# IO_function.net
KiCad netlist of a schematic drawn in Altium Designer
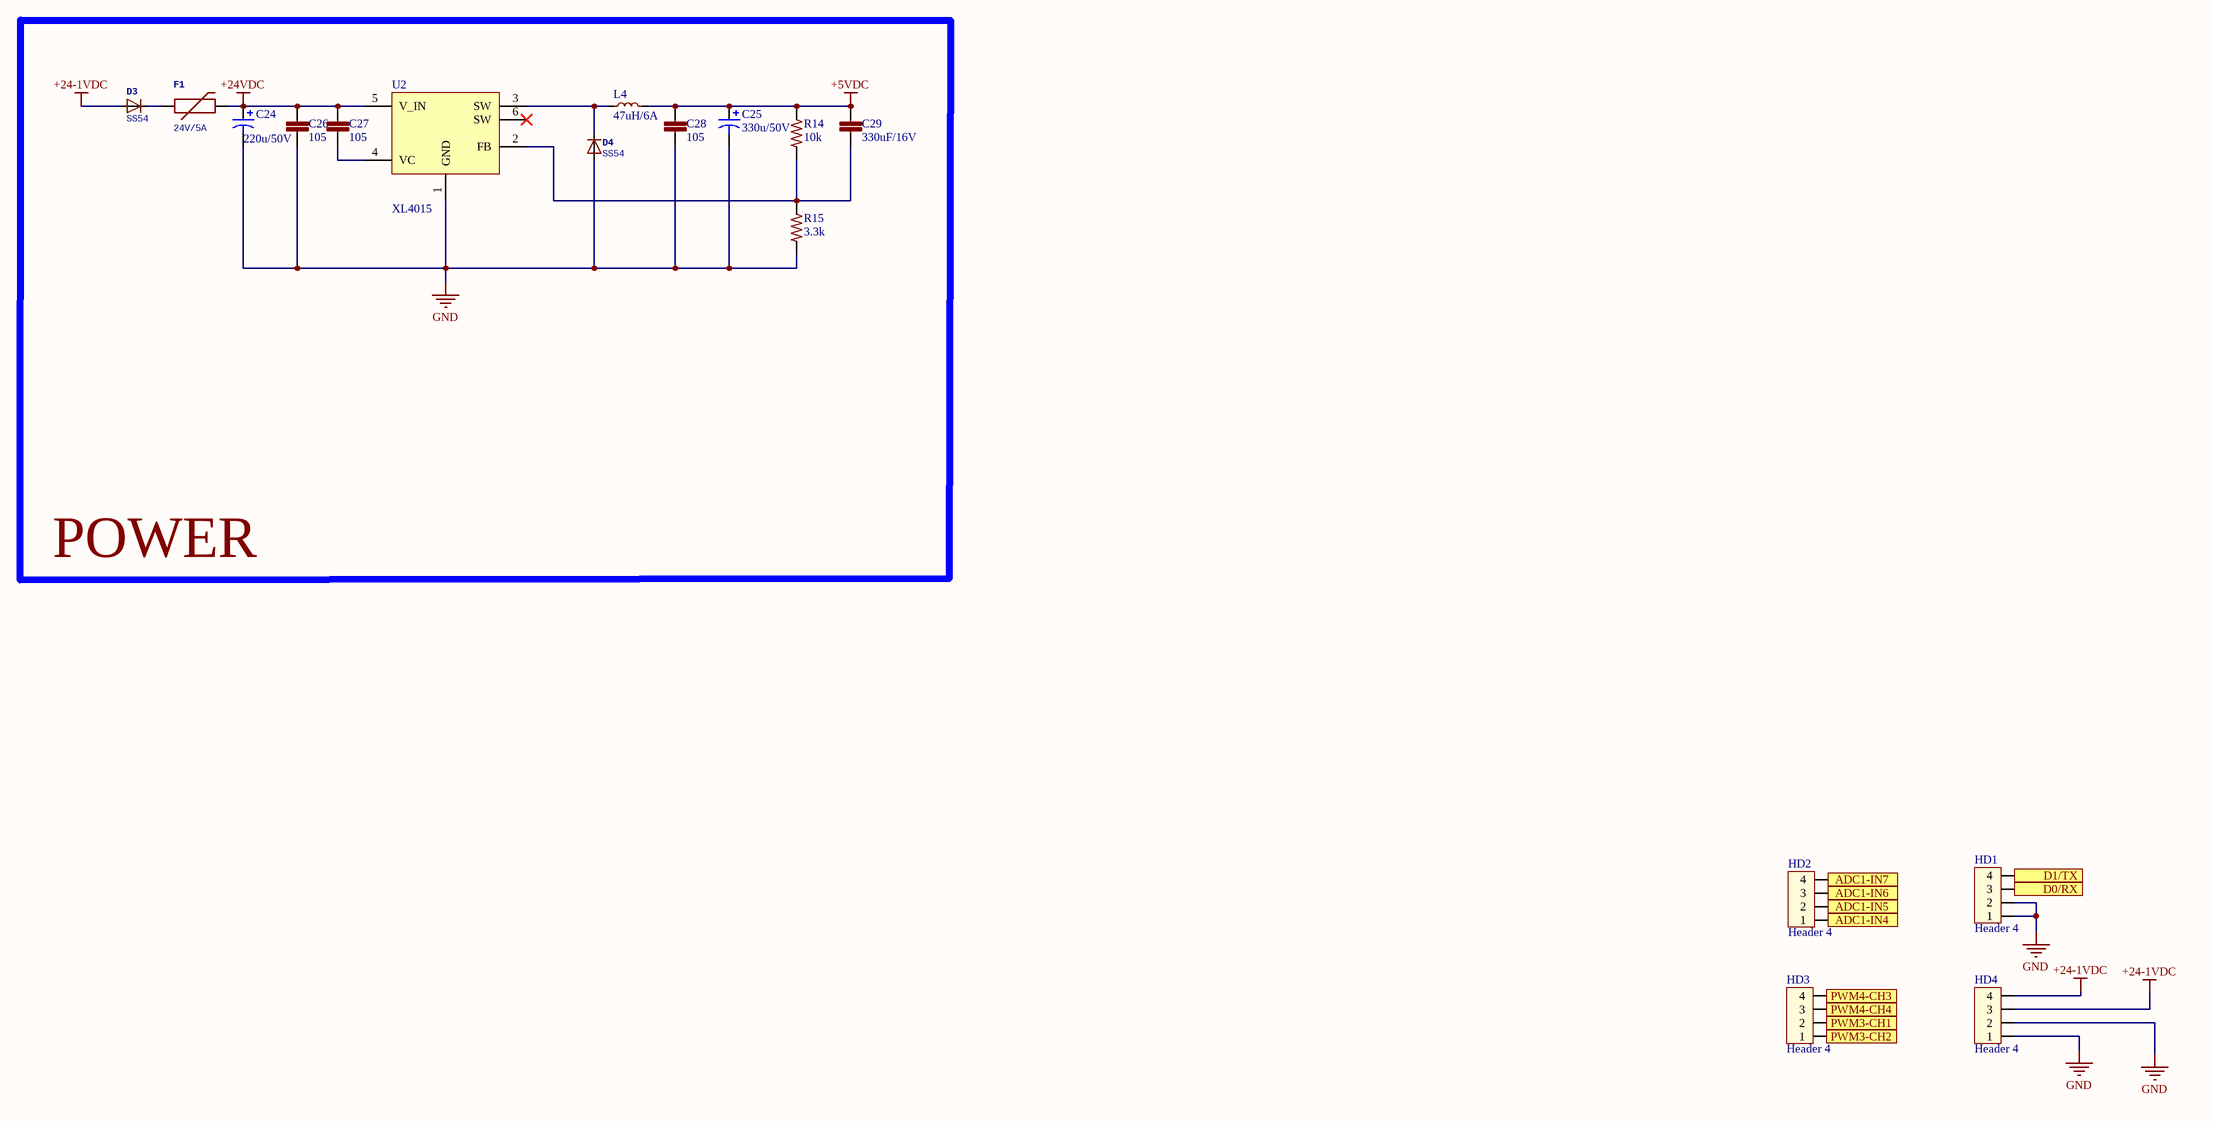
[diagram p0: IO_function.SchDoc]

(export (version "E")
  (design (tool "Eeschema 10.0.6"))
  (components
    (comp (ref "C24")
      (value "220u/50V")
      (footprint "CAP_SMD_8x10")
      (libsource (lib "UzumakiIchiro_Library") (part "Cap_Pol"))
    )
    (comp (ref "C25")
      (value "330u/50V")
      (footprint "CAP_SMD_8x10")
      (libsource (lib "UzumakiIchiro_Library") (part "Cap_Pol"))
    )
    (comp (ref "C26")
      (value "105")
      (footprint "CAP_SMD0603")
      (libsource (lib "UzumakiIchiro_Library") (part "Cap"))
    )
    (comp (ref "C27")
      (value "105")
      (footprint "CAP_SMD0603")
      (libsource (lib "UzumakiIchiro_Library") (part "Cap"))
    )
    (comp (ref "C28")
      (value "105")
      (footprint "CAP_SMD0603")
      (libsource (lib "UzumakiIchiro_Library") (part "Cap"))
    )
    (comp (ref "C29")
      (value "330uF/16V")
      (footprint "CAP_SMD0603")
      (libsource (lib "UzumakiIchiro_Library") (part "Cap"))
    )
    (comp (ref "D3")
      (value "SS54")
      (footprint "SMB")
      (libsource (lib "UzumakiIchiro_Library") (part "DIODE"))
    )
    (comp (ref "D4")
      (value "SS54")
      (footprint "SMB")
      (libsource (lib "UzumakiIchiro_Library") (part "DIODE"))
    )
    (comp (ref "F1")
      (value "24V/5A")
      (footprint "1206")
      (libsource (lib "UzumakiIchiro_Library") (part "Fuse"))
    )
    (comp (ref "HD1")
      (value "Header 4")
      (footprint "HED4")
      (description "Header 4 (Green)")
      (libsource (lib "syhaunguyen") (part "Hed4"))
    )
    (comp (ref "HD2")
      (value "Header 4")
      (footprint "HED4")
      (description "Header 4 (Green)")
      (libsource (lib "syhaunguyen") (part "Hed4"))
    )
    (comp (ref "HD3")
      (value "Header 4")
      (footprint "HED4")
      (description "Header 4 (Green)")
      (libsource (lib "syhaunguyen") (part "Hed4"))
    )
    (comp (ref "HD4")
      (value "Header 4")
      (footprint "HED4")
      (description "Header 4 (Green)")
      (libsource (lib "syhaunguyen") (part "Hed4"))
    )
    (comp (ref "L4")
      (value "47uH/6A")
      (footprint "Inductor_47uH_6A")
      (libsource (lib "UzumakiIchiro_Library") (part "Inductors"))
    )
    (comp (ref "R14")
      (value "10k")
      (footprint "RES_SMD0603")
      (libsource (lib "UzumakiIchiro_Library") (part "Resistor"))
    )
    (comp (ref "R15")
      (value "3.3k")
      (footprint "RES_SMD0603")
      (libsource (lib "UzumakiIchiro_Library") (part "Resistor"))
    )
    (comp (ref "U2")
      (value "XL4015")
      (footprint "TO-263-5")
      (libsource (lib "altium-import") (part "root_0_XL4015_"))
    )
  )
  (nets
    (net (code "1") (name "+5VDC") (class "Default")
      (node (ref "C25") (pin "1") (pinfunction "1_1") (pintype "passive"))
      (node (ref "C28") (pin "1") (pinfunction "1_1") (pintype "passive"))
      (node (ref "C29") (pin "1") (pinfunction "1_1") (pintype "passive"))
      (node (ref "L4") (pin "2") (pinfunction "2_2") (pintype "passive"))
      (node (ref "R14") (pin "1") (pinfunction "1_1") (pintype "passive"))
    )
    (net (code "2") (name "+24-1VDC") (class "Default")
      (node (ref "D3") (pin "1") (pinfunction "1_1") (pintype "passive"))
      (node (ref "HD4") (pin "3") (pinfunction "3_3") (pintype "passive"))
      (node (ref "HD4") (pin "4") (pinfunction "4_4") (pintype "passive"))
    )
    (net (code "3") (name "+24VDC") (class "Default")
      (node (ref "C24") (pin "1") (pinfunction "1_1") (pintype "passive"))
      (node (ref "C26") (pin "1") (pinfunction "1_1") (pintype "passive"))
      (node (ref "C27") (pin "1") (pinfunction "1_1") (pintype "passive"))
      (node (ref "F1") (pin "2") (pinfunction "2_2") (pintype "passive"))
      (node (ref "U2") (pin "5") (pinfunction "V_IN_5") (pintype "passive"))
    )
    (net (code "4") (name "/ADC1-IN4") (class "Default")
      (node (ref "HD2") (pin "1") (pinfunction "1_1") (pintype "passive"))
    )
    (net (code "5") (name "/ADC1-IN5") (class "Default")
      (node (ref "HD2") (pin "2") (pinfunction "2_2") (pintype "passive"))
    )
    (net (code "6") (name "/ADC1-IN6") (class "Default")
      (node (ref "HD2") (pin "3") (pinfunction "3_3") (pintype "passive"))
    )
    (net (code "7") (name "/ADC1-IN7") (class "Default")
      (node (ref "HD2") (pin "4") (pinfunction "4_4") (pintype "passive"))
    )
    (net (code "8") (name "/D0{slash}RX") (class "Default")
      (node (ref "HD1") (pin "3") (pinfunction "3_3") (pintype "passive"))
    )
    (net (code "9") (name "/D1{slash}TX") (class "Default")
      (node (ref "HD1") (pin "4") (pinfunction "4_4") (pintype "passive"))
    )
    (net (code "11") (name "/PWM3-CH1") (class "Default")
      (node (ref "HD3") (pin "2") (pinfunction "2_2") (pintype "passive"))
    )
    (net (code "12") (name "/PWM3-CH2") (class "Default")
      (node (ref "HD3") (pin "1") (pinfunction "1_1") (pintype "passive"))
    )
    (net (code "13") (name "/PWM4-CH3") (class "Default")
      (node (ref "HD3") (pin "4") (pinfunction "4_4") (pintype "passive"))
    )
    (net (code "14") (name "/PWM4-CH4") (class "Default")
      (node (ref "HD3") (pin "3") (pinfunction "3_3") (pintype "passive"))
    )
    (net (code "15") (name "GND") (class "Default")
      (node (ref "C24") (pin "2") (pinfunction "2_2") (pintype "passive"))
      (node (ref "C25") (pin "2") (pinfunction "2_2") (pintype "passive"))
      (node (ref "C26") (pin "2") (pinfunction "2_2") (pintype "passive"))
      (node (ref "C28") (pin "2") (pinfunction "2_2") (pintype "passive"))
      (node (ref "D4") (pin "1") (pinfunction "1_1") (pintype "passive"))
      (node (ref "HD1") (pin "1") (pinfunction "1_1") (pintype "passive"))
      (node (ref "HD1") (pin "2") (pinfunction "2_2") (pintype "passive"))
      (node (ref "HD4") (pin "1") (pinfunction "1_1") (pintype "passive"))
      (node (ref "HD4") (pin "2") (pinfunction "2_2") (pintype "passive"))
      (node (ref "R15") (pin "2") (pinfunction "2_2") (pintype "passive"))
      (node (ref "U2") (pin "1") (pinfunction "GND_1") (pintype "passive"))
    )
    (net (code "16") (name "Net-(D3-Pad2)") (class "Default")
      (node (ref "D3") (pin "2") (pinfunction "2_2") (pintype "passive"))
      (node (ref "F1") (pin "1") (pinfunction "1_1") (pintype "passive"))
    )
    (net (code "17") (name "Net-(D4-Pad2)") (class "Default")
      (node (ref "D4") (pin "2") (pinfunction "2_2") (pintype "passive"))
      (node (ref "L4") (pin "1") (pinfunction "1_1") (pintype "passive"))
      (node (ref "U2") (pin "3") (pinfunction "SW_3") (pintype "passive"))
    )
    (net (code "18") (name "Net-(U2-FB)") (class "Default")
      (node (ref "C29") (pin "2") (pinfunction "2_2") (pintype "passive"))
      (node (ref "R14") (pin "2") (pinfunction "2_2") (pintype "passive"))
      (node (ref "R15") (pin "1") (pinfunction "1_1") (pintype "passive"))
      (node (ref "U2") (pin "2") (pinfunction "FB_2") (pintype "passive"))
    )
    (net (code "19") (name "Net-(U2-VC)") (class "Default")
      (node (ref "C27") (pin "2") (pinfunction "2_2") (pintype "passive"))
      (node (ref "U2") (pin "4") (pinfunction "VC_4") (pintype "passive"))
    )
    (net (code "20") (name "unconnected-(U2-SW-Pad6)") (class "Default")
      (node (ref "U2") (pin "6") (pinfunction "SW_6") (pintype "passive+no_connect"))
    )
  )
)
